# 05_RPI_STROAGE.net
KiCad netlist of a schematic drawn in Altium Designer
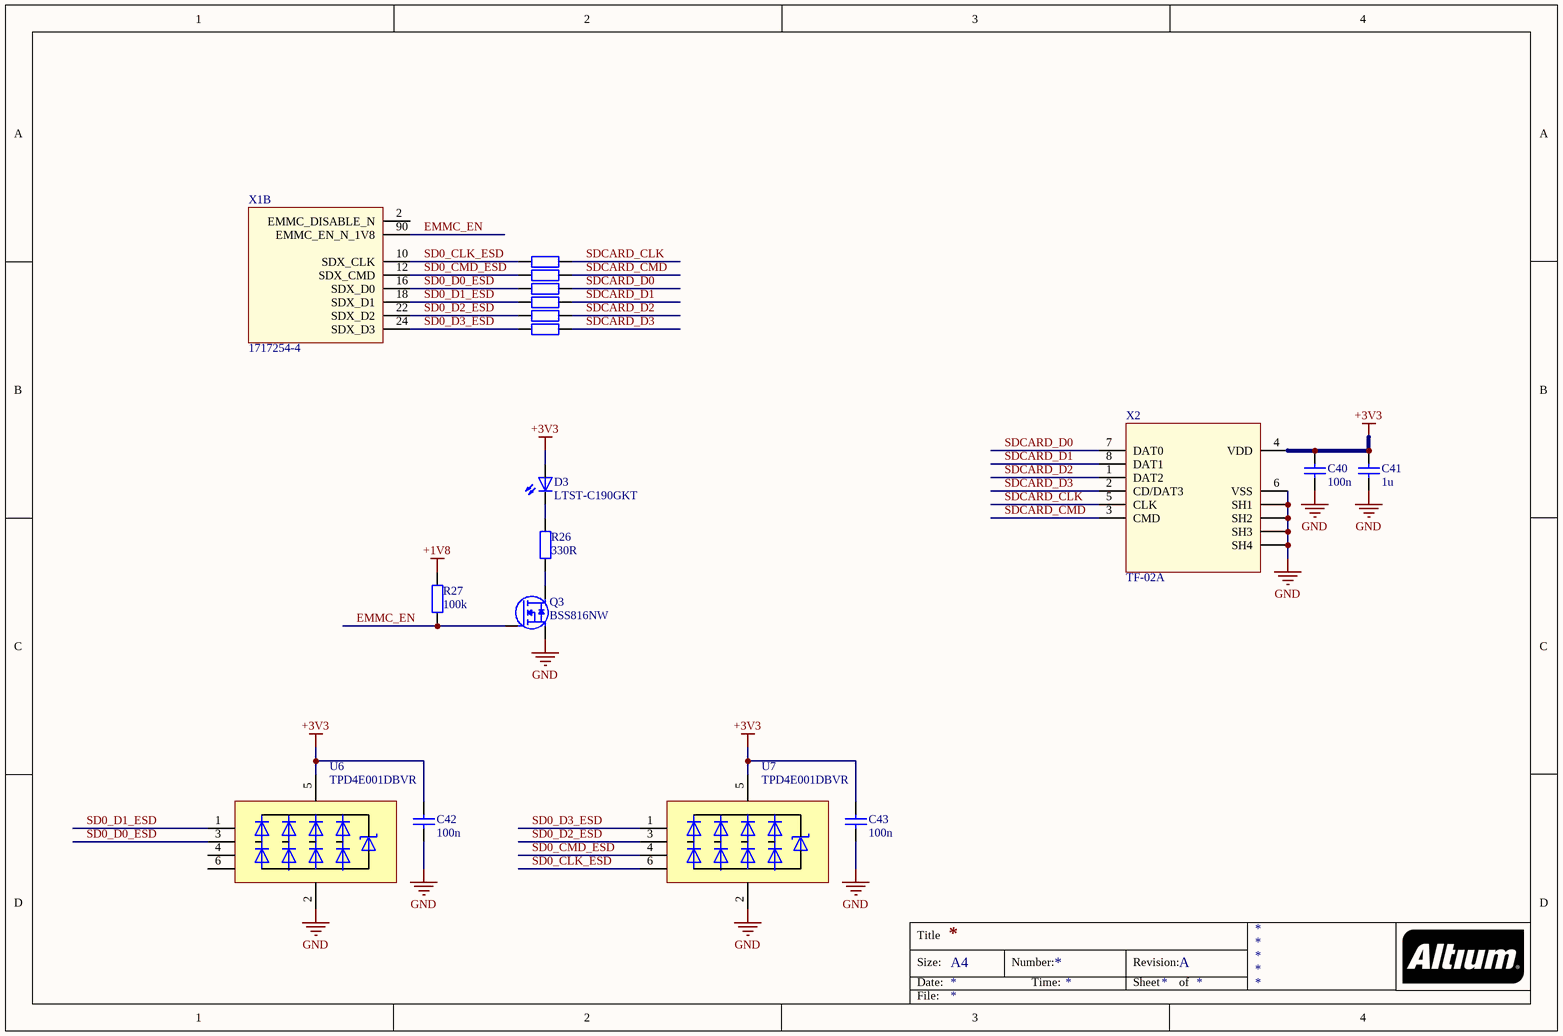
[diagram p0: 05_RPI_STROAGE.SchDoc]

(export (version "E")
  (design (tool "Eeschema 10.0.6"))
  (components
    (comp (ref "C40")
      (value "100n")
      (footprint "C0603_IPC_HD")
      (description "CAP CER 0.1UF 16V X7R 0603")
      (fields
        (field (name "MANUFACTURER") "Samsung Electro-Mechanics")
        (field (name "MANUFACTURER PART NUMBER") "CL10B104KO8NNNC")
      )
      (libsource (lib "alfasat_lib") (part "CL10B104KO8NNNC"))
    )
    (comp (ref "C41")
      (value "1u")
      (footprint "C0603_IPC_HD")
      (description "CAP CER 1UF 16V X7R 0603")
      (fields
        (field (name "MANUFACTURER") "Samsung Electro-Mechanics")
        (field (name "MANUFACTURER PART NUMBER") "CL10B105MO8NNWC")
      )
      (libsource (lib "alfasat_lib") (part "CL10B105MO8NNWC"))
    )
    (comp (ref "C42")
      (value "100n")
      (footprint "C0603_IPC_HD")
      (description "CAP CER 0.1UF 16V X7R 0603")
      (fields
        (field (name "MANUFACTURER") "Samsung Electro-Mechanics")
        (field (name "MANUFACTURER PART NUMBER") "CL10B104KO8NNNC")
      )
      (libsource (lib "alfasat_lib") (part "CL10B104KO8NNNC"))
    )
    (comp (ref "C43")
      (value "100n")
      (footprint "C0603_IPC_HD")
      (description "CAP CER 0.1UF 16V X7R 0603")
      (fields
        (field (name "MANUFACTURER") "Samsung Electro-Mechanics")
        (field (name "MANUFACTURER PART NUMBER") "CL10B104KO8NNNC")
      )
      (libsource (lib "alfasat_lib") (part "CL10B104KO8NNNC"))
    )
    (comp (ref "D3")
      (value "LTST-C190GKT")
      (footprint "LED_0603")
      (description "LED GREEN CLEAR CHIP SMD 0603")
      (fields (field (name "MANUFACTURER") "Lite-On Inc."))
      (libsource (lib "alfasat_lib") (part "LTST-C190GKT"))
    )
    (comp (ref "Q3")
      (value "BSS816NW")
      (footprint "SOT323")
      (description "N-Channel Logic Level Enhancement Mode Field Effect Transistor")
      (fields (field (name "MANUFACTURER") "Infineon Technologies"))
      (libsource (lib "alfasat_lib") (part "BSS816"))
    )
    (comp (ref "R20")
      (value "22R")
      (footprint "R0603_IPC_MD")
      (description "RES SMD 22 OHM 5% 1/10W 0603")
      (fields
        (field (name "MANUFACTURER") "Bourns Inc.")
        (field (name "MANUFACTURER PART NUMBER") "CR0603-JW-220ELF")
      )
      (libsource (lib "alfasat_lib") (part "CR0603-JW-220ELF"))
    )
    (comp (ref "R21")
      (value "22R")
      (footprint "R0603_IPC_MD")
      (description "RES SMD 22 OHM 5% 1/10W 0603")
      (fields
        (field (name "MANUFACTURER") "Bourns Inc.")
        (field (name "MANUFACTURER PART NUMBER") "CR0603-JW-220ELF")
      )
      (libsource (lib "alfasat_lib") (part "CR0603-JW-220ELF"))
    )
    (comp (ref "R22")
      (value "22R")
      (footprint "R0603_IPC_MD")
      (description "RES SMD 22 OHM 5% 1/10W 0603")
      (fields
        (field (name "MANUFACTURER") "Bourns Inc.")
        (field (name "MANUFACTURER PART NUMBER") "CR0603-JW-220ELF")
      )
      (libsource (lib "alfasat_lib") (part "CR0603-JW-220ELF"))
    )
    (comp (ref "R23")
      (value "22R")
      (footprint "R0603_IPC_MD")
      (description "RES SMD 22 OHM 5% 1/10W 0603")
      (fields
        (field (name "MANUFACTURER") "Bourns Inc.")
        (field (name "MANUFACTURER PART NUMBER") "CR0603-JW-220ELF")
      )
      (libsource (lib "alfasat_lib") (part "CR0603-JW-220ELF"))
    )
    (comp (ref "R24")
      (value "22R")
      (footprint "R0603_IPC_MD")
      (description "RES SMD 22 OHM 5% 1/10W 0603")
      (fields
        (field (name "MANUFACTURER") "Bourns Inc.")
        (field (name "MANUFACTURER PART NUMBER") "CR0603-JW-220ELF")
      )
      (libsource (lib "alfasat_lib") (part "CR0603-JW-220ELF"))
    )
    (comp (ref "R25")
      (value "22R")
      (footprint "R0603_IPC_MD")
      (description "RES SMD 22 OHM 5% 1/10W 0603")
      (fields
        (field (name "MANUFACTURER") "Bourns Inc.")
        (field (name "MANUFACTURER PART NUMBER") "CR0603-JW-220ELF")
      )
      (libsource (lib "alfasat_lib") (part "CR0603-JW-220ELF"))
    )
    (comp (ref "R26")
      (value "330R")
      (footprint "R0603_IPC_MD")
      (description "RES SMD 330 OHM 5% 1/10W 0603")
      (fields
        (field (name "MANUFACTURER") "Bourns Inc.")
        (field (name "MANUFACTURER PART NUMBER") "CR0603-JW-331ELF")
      )
      (libsource (lib "alfasat_lib") (part "CR0603-JW-331ELF"))
    )
    (comp (ref "R27")
      (value "100k")
      (footprint "R0603_IPC_MD")
      (description "RES 100K OHM 1% 1/10W 0603")
      (fields
        (field (name "MANUFACTURER") "Bourns Inc.")
        (field (name "MANUFACTURER PART NUMBER") "RMCF0603FT100K")
      )
      (libsource (lib "alfasat_lib") (part "RMCF0603FT100K"))
    )
    (comp (ref "U6")
      (value "TPD4E001DBVR")
      (footprint "SOT23-6")
      (description "4x TVS DIODE 5.5V SOT23-6")
      (fields (field (name "MANUFACTURER") "TI"))
      (libsource (lib "alfasat_lib") (part "TPD4E001DBVR"))
    )
    (comp (ref "U7")
      (value "TPD4E001DBVR")
      (footprint "SOT23-6")
      (description "4x TVS DIODE 5.5V SOT23-6")
      (fields (field (name "MANUFACTURER") "TI"))
      (libsource (lib "alfasat_lib") (part "TPD4E001DBVR"))
    )
    (comp (ref "X1")
      (value "1717254-4")
      (footprint "1717254-1")
      (description "CONN SKT SODIMM 200POS R/A SMD")
      (fields (field (name "MANUFACTURER") "TE Connectivity AMP Connectors"))
      (libsource (lib "alfasat_lib") (part "Raspberry CM Connector"))
    )
    (comp (ref "X2")
      (value "TF-02A")
      (footprint "TF-02A")
      (description "CONN MICRO SD CARD")
      (fields (field (name "MANUFACTURER") "Korean Hroparts Elec"))
      (libsource (lib "alfasat_lib") (part "TF-02A"))
    )
  )
  (nets
    (net (code "1") (name "+1V8") (class "Default")
      (node (ref "R27") (pin "2") (pinfunction "2_2") (pintype "passive"))
    )
    (net (code "2") (name "+3V3") (class "Default")
      (node (ref "C40") (pin "2") (pinfunction "2_2") (pintype "passive"))
      (node (ref "C41") (pin "2") (pinfunction "2_2") (pintype "passive"))
      (node (ref "C42") (pin "2") (pinfunction "2_2") (pintype "passive"))
      (node (ref "C43") (pin "2") (pinfunction "2_2") (pintype "passive"))
      (node (ref "D3") (pin "2") (pinfunction "A_2") (pintype "passive"))
      (node (ref "U6") (pin "5") (pinfunction "VCC_5") (pintype "power_in"))
      (node (ref "U7") (pin "5") (pinfunction "VCC_5") (pintype "power_in"))
      (node (ref "X2") (pin "4") (pinfunction "VDD_4") (pintype "passive"))
    )
    (net (code "3") (name "/EMMC_EN") (class "Default")
      (node (ref "Q3") (pin "1") (pinfunction "G_1") (pintype "passive"))
      (node (ref "R27") (pin "1") (pinfunction "1_1") (pintype "passive"))
      (node (ref "X1") (pin "90") (pinfunction "EMMC_EN_N_1V8_90") (pintype "passive"))
    )
    (net (code "4") (name "/SD0_CLK_ESD") (class "Default")
      (node (ref "R20") (pin "1") (pinfunction "1_1") (pintype "passive"))
      (node (ref "U7") (pin "6") (pinfunction "IO4_6") (pintype "passive"))
      (node (ref "X1") (pin "10") (pinfunction "SDX_CLK_10") (pintype "passive"))
    )
    (net (code "5") (name "/SD0_CMD_ESD") (class "Default")
      (node (ref "R21") (pin "1") (pinfunction "1_1") (pintype "passive"))
      (node (ref "U7") (pin "4") (pinfunction "IO3_4") (pintype "passive"))
      (node (ref "X1") (pin "12") (pinfunction "SDX_CMD_12") (pintype "passive"))
    )
    (net (code "6") (name "/SD0_D0_ESD") (class "Default")
      (node (ref "R22") (pin "1") (pinfunction "1_1") (pintype "passive"))
      (node (ref "U6") (pin "3") (pinfunction "IO2_3") (pintype "passive"))
      (node (ref "X1") (pin "16") (pinfunction "SDX_D0_16") (pintype "passive"))
    )
    (net (code "7") (name "/SD0_D1_ESD") (class "Default")
      (node (ref "R23") (pin "1") (pinfunction "1_1") (pintype "passive"))
      (node (ref "U6") (pin "1") (pinfunction "IO1_1") (pintype "passive"))
      (node (ref "X1") (pin "18") (pinfunction "SDX_D1_18") (pintype "passive"))
    )
    (net (code "8") (name "/SD0_D2_ESD") (class "Default")
      (node (ref "R24") (pin "1") (pinfunction "1_1") (pintype "passive"))
      (node (ref "U7") (pin "3") (pinfunction "IO2_3") (pintype "passive"))
      (node (ref "X1") (pin "22") (pinfunction "SDX_D2_22") (pintype "passive"))
    )
    (net (code "9") (name "/SD0_D3_ESD") (class "Default")
      (node (ref "R25") (pin "1") (pinfunction "1_1") (pintype "passive"))
      (node (ref "U7") (pin "1") (pinfunction "IO1_1") (pintype "passive"))
      (node (ref "X1") (pin "24") (pinfunction "SDX_D3_24") (pintype "passive"))
    )
    (net (code "10") (name "/SDCARD_CLK") (class "Default")
      (node (ref "R20") (pin "2") (pinfunction "2_2") (pintype "passive"))
      (node (ref "X2") (pin "5") (pinfunction "CLK_5") (pintype "passive"))
    )
    (net (code "11") (name "/SDCARD_CMD") (class "Default")
      (node (ref "R21") (pin "2") (pinfunction "2_2") (pintype "passive"))
      (node (ref "X2") (pin "3") (pinfunction "CMD_3") (pintype "passive"))
    )
    (net (code "12") (name "/SDCARD_D0") (class "Default")
      (node (ref "R22") (pin "2") (pinfunction "2_2") (pintype "passive"))
      (node (ref "X2") (pin "7") (pinfunction "DAT0_7") (pintype "passive"))
    )
    (net (code "13") (name "/SDCARD_D1") (class "Default")
      (node (ref "R23") (pin "2") (pinfunction "2_2") (pintype "passive"))
      (node (ref "X2") (pin "8") (pinfunction "DAT1_8") (pintype "passive"))
    )
    (net (code "14") (name "/SDCARD_D2") (class "Default")
      (node (ref "R24") (pin "2") (pinfunction "2_2") (pintype "passive"))
      (node (ref "X2") (pin "1") (pinfunction "DAT2_1") (pintype "passive"))
    )
    (net (code "15") (name "/SDCARD_D3") (class "Default")
      (node (ref "R25") (pin "2") (pinfunction "2_2") (pintype "passive"))
      (node (ref "X2") (pin "2") (pinfunction "CD/DAT3_2") (pintype "passive"))
    )
    (net (code "16") (name "GND") (class "Default")
      (node (ref "C40") (pin "1") (pinfunction "1_1") (pintype "passive"))
      (node (ref "C41") (pin "1") (pinfunction "1_1") (pintype "passive"))
      (node (ref "C42") (pin "1") (pinfunction "1_1") (pintype "passive"))
      (node (ref "C43") (pin "1") (pinfunction "1_1") (pintype "passive"))
      (node (ref "Q3") (pin "2") (pinfunction "S_2") (pintype "passive"))
      (node (ref "U6") (pin "2") (pinfunction "GND_2") (pintype "power_in"))
      (node (ref "U7") (pin "2") (pinfunction "GND_2") (pintype "power_in"))
      (node (ref "X2") (pin "10") (pinfunction "SH2_10") (pintype "passive"))
      (node (ref "X2") (pin "11") (pinfunction "SH3_11") (pintype "passive"))
      (node (ref "X2") (pin "12") (pinfunction "SH4_12") (pintype "passive"))
      (node (ref "X2") (pin "6") (pinfunction "VSS_6") (pintype "passive"))
      (node (ref "X2") (pin "9") (pinfunction "SH1_9") (pintype "passive"))
    )
    (net (code "17") (name "Net-(D3-C)") (class "Default")
      (node (ref "D3") (pin "1") (pinfunction "C_1") (pintype "passive"))
      (node (ref "R26") (pin "2") (pinfunction "2_2") (pintype "passive"))
    )
    (net (code "18") (name "Net-(Q3-D)") (class "Default")
      (node (ref "Q3") (pin "3") (pinfunction "D_3") (pintype "passive"))
      (node (ref "R26") (pin "1") (pinfunction "1_1") (pintype "passive"))
    )
    (net (code "19") (name "unconnected-(U6-IO3-Pad4)") (class "Default")
      (node (ref "U6") (pin "4") (pinfunction "IO3_4") (pintype "passive"))
    )
    (net (code "20") (name "unconnected-(U6-IO4-Pad6)") (class "Default")
      (node (ref "U6") (pin "6") (pinfunction "IO4_6") (pintype "passive"))
    )
    (net (code "21") (name "unconnected-(X1B-EMMC_DISABLE_N-Pad2)") (class "Default")
      (node (ref "X1") (pin "2") (pinfunction "EMMC_DISABLE_N_2") (pintype "passive"))
    )
  )
)
